# Memory_Chips_1_to_4.net
KiCad netlist of a schematic drawn in Altium Designer
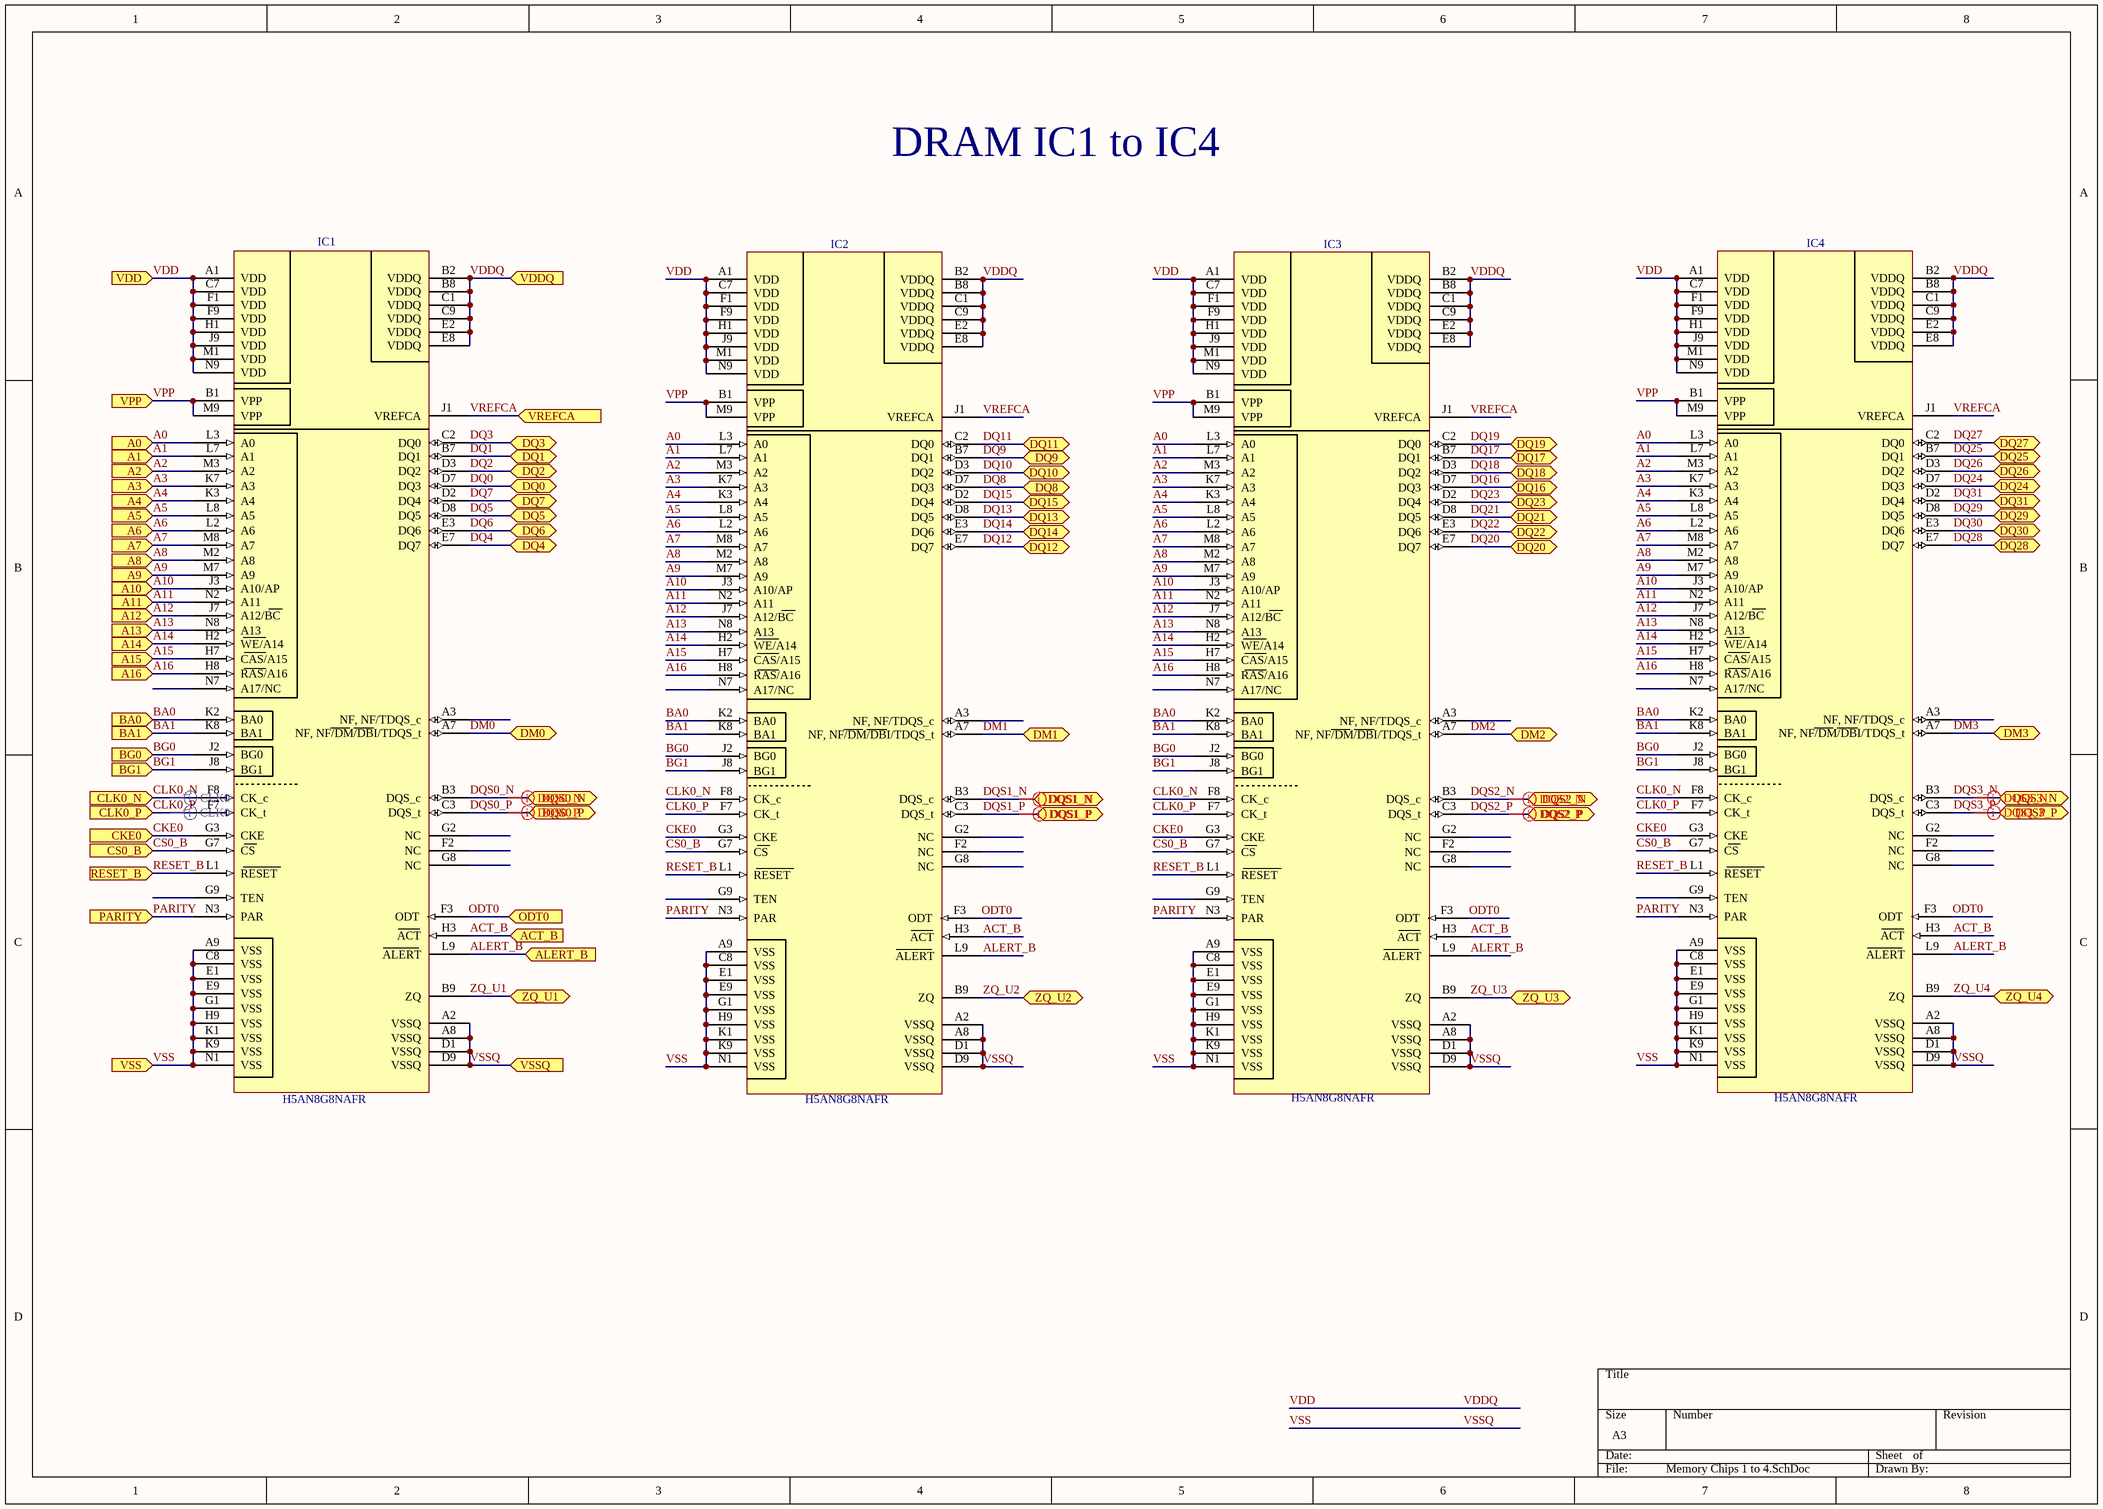
[diagram p0: Memory Chips 1 to 4.SchDoc]

(export (version "E")
  (design (tool "Eeschema 10.0.6"))
  (components
    (comp (ref "IC1")
      (value "H5AN8G8NAFR")
      (footprint "H5AN8G8NAFR")
      (libsource (lib "RouterIntLib") (part "H5AN8G8NAFR"))
    )
    (comp (ref "IC2")
      (value "H5AN8G8NAFR")
      (footprint "H5AN8G8NAFR")
      (libsource (lib "RouterIntLib") (part "H5AN8G8NAFR"))
    )
    (comp (ref "IC3")
      (value "H5AN8G8NAFR")
      (footprint "H5AN8G8NAFR")
      (libsource (lib "RouterIntLib") (part "H5AN8G8NAFR"))
    )
    (comp (ref "IC4")
      (value "H5AN8G8NAFR")
      (footprint "H5AN8G8NAFR")
      (libsource (lib "RouterIntLib") (part "H5AN8G8NAFR"))
    )
  )
  (nets
    (net (code "1") (name "/A0") (class "Default")
      (node (ref "IC1") (pin "L3") (pinfunction "A0_L3") (pintype "input"))
      (node (ref "IC2") (pin "L3") (pinfunction "A0_L3") (pintype "input"))
      (node (ref "IC3") (pin "L3") (pinfunction "A0_L3") (pintype "input"))
      (node (ref "IC4") (pin "L3") (pinfunction "A0_L3") (pintype "input"))
    )
    (net (code "2") (name "/A1") (class "Default")
      (node (ref "IC1") (pin "L7") (pinfunction "A1_L7") (pintype "input"))
      (node (ref "IC2") (pin "L7") (pinfunction "A1_L7") (pintype "input"))
      (node (ref "IC3") (pin "L7") (pinfunction "A1_L7") (pintype "input"))
      (node (ref "IC4") (pin "L7") (pinfunction "A1_L7") (pintype "input"))
    )
    (net (code "3") (name "/A2") (class "Default")
      (node (ref "IC1") (pin "M3") (pinfunction "A2_M3") (pintype "input"))
      (node (ref "IC2") (pin "M3") (pinfunction "A2_M3") (pintype "input"))
      (node (ref "IC3") (pin "M3") (pinfunction "A2_M3") (pintype "input"))
      (node (ref "IC4") (pin "M3") (pinfunction "A2_M3") (pintype "input"))
    )
    (net (code "4") (name "/A3") (class "Default")
      (node (ref "IC1") (pin "K7") (pinfunction "A3_K7") (pintype "input"))
      (node (ref "IC2") (pin "K7") (pinfunction "A3_K7") (pintype "input"))
      (node (ref "IC3") (pin "K7") (pinfunction "A3_K7") (pintype "input"))
      (node (ref "IC4") (pin "K7") (pinfunction "A3_K7") (pintype "input"))
    )
    (net (code "5") (name "/A4") (class "Default")
      (node (ref "IC1") (pin "K3") (pinfunction "A4_K3") (pintype "input"))
      (node (ref "IC2") (pin "K3") (pinfunction "A4_K3") (pintype "input"))
      (node (ref "IC3") (pin "K3") (pinfunction "A4_K3") (pintype "input"))
      (node (ref "IC4") (pin "K3") (pinfunction "A4_K3") (pintype "input"))
    )
    (net (code "6") (name "/A5") (class "Default")
      (node (ref "IC1") (pin "L8") (pinfunction "A5_L8") (pintype "input"))
      (node (ref "IC2") (pin "L8") (pinfunction "A5_L8") (pintype "input"))
      (node (ref "IC3") (pin "L8") (pinfunction "A5_L8") (pintype "input"))
      (node (ref "IC4") (pin "L8") (pinfunction "A5_L8") (pintype "input"))
    )
    (net (code "7") (name "/A6") (class "Default")
      (node (ref "IC1") (pin "L2") (pinfunction "A6_L2") (pintype "input"))
      (node (ref "IC2") (pin "L2") (pinfunction "A6_L2") (pintype "input"))
      (node (ref "IC3") (pin "L2") (pinfunction "A6_L2") (pintype "input"))
      (node (ref "IC4") (pin "L2") (pinfunction "A6_L2") (pintype "input"))
    )
    (net (code "8") (name "/A7") (class "Default")
      (node (ref "IC1") (pin "M8") (pinfunction "A7_M8") (pintype "input"))
      (node (ref "IC2") (pin "M8") (pinfunction "A7_M8") (pintype "input"))
      (node (ref "IC3") (pin "M8") (pinfunction "A7_M8") (pintype "input"))
      (node (ref "IC4") (pin "M8") (pinfunction "A7_M8") (pintype "input"))
    )
    (net (code "9") (name "/A8") (class "Default")
      (node (ref "IC1") (pin "M2") (pinfunction "A8_M2") (pintype "input"))
      (node (ref "IC2") (pin "M2") (pinfunction "A8_M2") (pintype "input"))
      (node (ref "IC3") (pin "M2") (pinfunction "A8_M2") (pintype "input"))
      (node (ref "IC4") (pin "M2") (pinfunction "A8_M2") (pintype "input"))
    )
    (net (code "10") (name "/A9") (class "Default")
      (node (ref "IC1") (pin "M7") (pinfunction "A9_M7") (pintype "input"))
      (node (ref "IC2") (pin "M7") (pinfunction "A9_M7") (pintype "input"))
      (node (ref "IC3") (pin "M7") (pinfunction "A9_M7") (pintype "input"))
      (node (ref "IC4") (pin "M7") (pinfunction "A9_M7") (pintype "input"))
    )
    (net (code "11") (name "/A10") (class "Default")
      (node (ref "IC1") (pin "J3") (pinfunction "A10/AP_J3") (pintype "input"))
      (node (ref "IC2") (pin "J3") (pinfunction "A10/AP_J3") (pintype "input"))
      (node (ref "IC3") (pin "J3") (pinfunction "A10/AP_J3") (pintype "input"))
      (node (ref "IC4") (pin "J3") (pinfunction "A10/AP_J3") (pintype "input"))
    )
    (net (code "12") (name "/A11") (class "Default")
      (node (ref "IC1") (pin "N2") (pinfunction "A11_N2") (pintype "input"))
      (node (ref "IC2") (pin "N2") (pinfunction "A11_N2") (pintype "input"))
      (node (ref "IC3") (pin "N2") (pinfunction "A11_N2") (pintype "input"))
      (node (ref "IC4") (pin "N2") (pinfunction "A11_N2") (pintype "input"))
    )
    (net (code "13") (name "/A12") (class "Default")
      (node (ref "IC1") (pin "J7") (pinfunction "A12/BC_J7") (pintype "input"))
      (node (ref "IC2") (pin "J7") (pinfunction "A12/BC_J7") (pintype "input"))
      (node (ref "IC3") (pin "J7") (pinfunction "A12/BC_J7") (pintype "input"))
      (node (ref "IC4") (pin "J7") (pinfunction "A12/BC_J7") (pintype "input"))
    )
    (net (code "14") (name "/A13") (class "Default")
      (node (ref "IC1") (pin "N8") (pinfunction "A13_N8") (pintype "input"))
      (node (ref "IC2") (pin "N8") (pinfunction "A13_N8") (pintype "input"))
      (node (ref "IC3") (pin "N8") (pinfunction "A13_N8") (pintype "input"))
      (node (ref "IC4") (pin "N8") (pinfunction "A13_N8") (pintype "input"))
    )
    (net (code "15") (name "/A14") (class "Default")
      (node (ref "IC1") (pin "H2") (pinfunction "WE/A14_H2") (pintype "input"))
      (node (ref "IC2") (pin "H2") (pinfunction "WE/A14_H2") (pintype "input"))
      (node (ref "IC3") (pin "H2") (pinfunction "WE/A14_H2") (pintype "input"))
      (node (ref "IC4") (pin "H2") (pinfunction "WE/A14_H2") (pintype "input"))
    )
    (net (code "16") (name "/A15") (class "Default")
      (node (ref "IC1") (pin "H7") (pinfunction "CAS/A15_H7") (pintype "input"))
      (node (ref "IC2") (pin "H7") (pinfunction "CAS/A15_H7") (pintype "input"))
      (node (ref "IC3") (pin "H7") (pinfunction "CAS/A15_H7") (pintype "input"))
      (node (ref "IC4") (pin "H7") (pinfunction "CAS/A15_H7") (pintype "input"))
    )
    (net (code "17") (name "/A16") (class "Default")
      (node (ref "IC1") (pin "H8") (pinfunction "RAS/A16_H8") (pintype "input"))
      (node (ref "IC2") (pin "H8") (pinfunction "RAS/A16_H8") (pintype "input"))
      (node (ref "IC3") (pin "H8") (pinfunction "RAS/A16_H8") (pintype "input"))
      (node (ref "IC4") (pin "H8") (pinfunction "RAS/A16_H8") (pintype "input"))
    )
    (net (code "18") (name "/ACT_B") (class "Default")
      (node (ref "IC1") (pin "H3") (pinfunction "ACT_H3") (pintype "input"))
      (node (ref "IC2") (pin "H3") (pinfunction "ACT_H3") (pintype "input"))
      (node (ref "IC3") (pin "H3") (pinfunction "ACT_H3") (pintype "input"))
      (node (ref "IC4") (pin "H3") (pinfunction "ACT_H3") (pintype "input"))
    )
    (net (code "19") (name "/ALERT_B") (class "Default")
      (node (ref "IC1") (pin "L9") (pinfunction "ALERT_L9") (pintype "passive"))
      (node (ref "IC2") (pin "L9") (pinfunction "ALERT_L9") (pintype "passive"))
      (node (ref "IC3") (pin "L9") (pinfunction "ALERT_L9") (pintype "passive"))
      (node (ref "IC4") (pin "L9") (pinfunction "ALERT_L9") (pintype "passive"))
    )
    (net (code "20") (name "/BA0") (class "Default")
      (node (ref "IC1") (pin "K2") (pinfunction "BA0_K2") (pintype "input"))
      (node (ref "IC2") (pin "K2") (pinfunction "BA0_K2") (pintype "input"))
      (node (ref "IC3") (pin "K2") (pinfunction "BA0_K2") (pintype "input"))
      (node (ref "IC4") (pin "K2") (pinfunction "BA0_K2") (pintype "input"))
    )
    (net (code "21") (name "/BA1") (class "Default")
      (node (ref "IC1") (pin "K8") (pinfunction "BA1_K8") (pintype "input"))
      (node (ref "IC2") (pin "K8") (pinfunction "BA1_K8") (pintype "input"))
      (node (ref "IC3") (pin "K8") (pinfunction "BA1_K8") (pintype "input"))
      (node (ref "IC4") (pin "K8") (pinfunction "BA1_K8") (pintype "input"))
    )
    (net (code "22") (name "/BG0") (class "Default")
      (node (ref "IC1") (pin "J2") (pinfunction "BG0_J2") (pintype "input"))
      (node (ref "IC2") (pin "J2") (pinfunction "BG0_J2") (pintype "input"))
      (node (ref "IC3") (pin "J2") (pinfunction "BG0_J2") (pintype "input"))
      (node (ref "IC4") (pin "J2") (pinfunction "BG0_J2") (pintype "input"))
    )
    (net (code "23") (name "/BG1") (class "Default")
      (node (ref "IC1") (pin "J8") (pinfunction "BG1_J8") (pintype "input"))
      (node (ref "IC2") (pin "J8") (pinfunction "BG1_J8") (pintype "input"))
      (node (ref "IC3") (pin "J8") (pinfunction "BG1_J8") (pintype "input"))
      (node (ref "IC4") (pin "J8") (pinfunction "BG1_J8") (pintype "input"))
    )
    (net (code "24") (name "/CKE0") (class "Default")
      (node (ref "IC1") (pin "G3") (pinfunction "CKE_G3") (pintype "input"))
      (node (ref "IC2") (pin "G3") (pinfunction "CKE_G3") (pintype "input"))
      (node (ref "IC3") (pin "G3") (pinfunction "CKE_G3") (pintype "input"))
      (node (ref "IC4") (pin "G3") (pinfunction "CKE_G3") (pintype "input"))
    )
    (net (code "25") (name "/CLK0_N") (class "Default")
      (node (ref "IC1") (pin "F8") (pinfunction "CK_c_F8") (pintype "input"))
      (node (ref "IC2") (pin "F8") (pinfunction "CK_c_F8") (pintype "input"))
      (node (ref "IC3") (pin "F8") (pinfunction "CK_c_F8") (pintype "input"))
      (node (ref "IC4") (pin "F8") (pinfunction "CK_c_F8") (pintype "input"))
    )
    (net (code "26") (name "/CLK0_P") (class "Default")
      (node (ref "IC1") (pin "F7") (pinfunction "CK_t_F7") (pintype "input"))
      (node (ref "IC2") (pin "F7") (pinfunction "CK_t_F7") (pintype "input"))
      (node (ref "IC3") (pin "F7") (pinfunction "CK_t_F7") (pintype "input"))
      (node (ref "IC4") (pin "F7") (pinfunction "CK_t_F7") (pintype "input"))
    )
    (net (code "27") (name "/CS0_B") (class "Default")
      (node (ref "IC1") (pin "G7") (pinfunction "CS_G7") (pintype "input"))
      (node (ref "IC2") (pin "G7") (pinfunction "CS_G7") (pintype "input"))
      (node (ref "IC3") (pin "G7") (pinfunction "CS_G7") (pintype "input"))
      (node (ref "IC4") (pin "G7") (pinfunction "CS_G7") (pintype "input"))
    )
    (net (code "28") (name "/DM0") (class "Default")
      (node (ref "IC1") (pin "A7") (pinfunction "NF,_NF/DM/DBI/TDQS_t_A7") (pintype "bidirectional"))
    )
    (net (code "29") (name "/DM1") (class "Default")
      (node (ref "IC2") (pin "A7") (pinfunction "NF,_NF/DM/DBI/TDQS_t_A7") (pintype "bidirectional"))
    )
    (net (code "30") (name "/DM2") (class "Default")
      (node (ref "IC3") (pin "A7") (pinfunction "NF,_NF/DM/DBI/TDQS_t_A7") (pintype "bidirectional"))
    )
    (net (code "31") (name "/DM3") (class "Default")
      (node (ref "IC4") (pin "A7") (pinfunction "NF,_NF/DM/DBI/TDQS_t_A7") (pintype "bidirectional"))
    )
    (net (code "32") (name "/DQ0") (class "Default")
      (node (ref "IC1") (pin "D7") (pinfunction "DQ3_D7") (pintype "bidirectional"))
    )
    (net (code "33") (name "/DQ1") (class "Default")
      (node (ref "IC1") (pin "B7") (pinfunction "DQ1_B7") (pintype "bidirectional"))
    )
    (net (code "34") (name "/DQ2") (class "Default")
      (node (ref "IC1") (pin "D3") (pinfunction "DQ2_D3") (pintype "bidirectional"))
    )
    (net (code "35") (name "/DQ3") (class "Default")
      (node (ref "IC1") (pin "C2") (pinfunction "DQ0_C2") (pintype "bidirectional"))
    )
    (net (code "36") (name "/DQ4") (class "Default")
      (node (ref "IC1") (pin "E7") (pinfunction "DQ7_E7") (pintype "bidirectional"))
    )
    (net (code "37") (name "/DQ5") (class "Default")
      (node (ref "IC1") (pin "D8") (pinfunction "DQ5_D8") (pintype "bidirectional"))
    )
    (net (code "38") (name "/DQ6") (class "Default")
      (node (ref "IC1") (pin "E3") (pinfunction "DQ6_E3") (pintype "bidirectional"))
    )
    (net (code "39") (name "/DQ7") (class "Default")
      (node (ref "IC1") (pin "D2") (pinfunction "DQ4_D2") (pintype "bidirectional"))
    )
    (net (code "40") (name "/DQ8") (class "Default")
      (node (ref "IC2") (pin "D7") (pinfunction "DQ3_D7") (pintype "bidirectional"))
    )
    (net (code "41") (name "/DQ9") (class "Default")
      (node (ref "IC2") (pin "B7") (pinfunction "DQ1_B7") (pintype "bidirectional"))
    )
    (net (code "42") (name "/DQ10") (class "Default")
      (node (ref "IC2") (pin "D3") (pinfunction "DQ2_D3") (pintype "bidirectional"))
    )
    (net (code "43") (name "/DQ11") (class "Default")
      (node (ref "IC2") (pin "C2") (pinfunction "DQ0_C2") (pintype "bidirectional"))
    )
    (net (code "44") (name "/DQ12") (class "Default")
      (node (ref "IC2") (pin "E7") (pinfunction "DQ7_E7") (pintype "bidirectional"))
    )
    (net (code "45") (name "/DQ13") (class "Default")
      (node (ref "IC2") (pin "D8") (pinfunction "DQ5_D8") (pintype "bidirectional"))
    )
    (net (code "46") (name "/DQ14") (class "Default")
      (node (ref "IC2") (pin "E3") (pinfunction "DQ6_E3") (pintype "bidirectional"))
    )
    (net (code "47") (name "/DQ15") (class "Default")
      (node (ref "IC2") (pin "D2") (pinfunction "DQ4_D2") (pintype "bidirectional"))
    )
    (net (code "48") (name "/DQ16") (class "Default")
      (node (ref "IC3") (pin "D7") (pinfunction "DQ3_D7") (pintype "bidirectional"))
    )
    (net (code "49") (name "/DQ17") (class "Default")
      (node (ref "IC3") (pin "B7") (pinfunction "DQ1_B7") (pintype "bidirectional"))
    )
    (net (code "50") (name "/DQ18") (class "Default")
      (node (ref "IC3") (pin "D3") (pinfunction "DQ2_D3") (pintype "bidirectional"))
    )
    (net (code "51") (name "/DQ19") (class "Default")
      (node (ref "IC3") (pin "C2") (pinfunction "DQ0_C2") (pintype "bidirectional"))
    )
    (net (code "52") (name "/DQ20") (class "Default")
      (node (ref "IC3") (pin "E7") (pinfunction "DQ7_E7") (pintype "bidirectional"))
    )
    (net (code "53") (name "/DQ21") (class "Default")
      (node (ref "IC3") (pin "D8") (pinfunction "DQ5_D8") (pintype "bidirectional"))
    )
    (net (code "54") (name "/DQ22") (class "Default")
      (node (ref "IC3") (pin "E3") (pinfunction "DQ6_E3") (pintype "bidirectional"))
    )
    (net (code "55") (name "/DQ23") (class "Default")
      (node (ref "IC3") (pin "D2") (pinfunction "DQ4_D2") (pintype "bidirectional"))
    )
    (net (code "56") (name "/DQ24") (class "Default")
      (node (ref "IC4") (pin "D7") (pinfunction "DQ3_D7") (pintype "bidirectional"))
    )
    (net (code "57") (name "/DQ25") (class "Default")
      (node (ref "IC4") (pin "B7") (pinfunction "DQ1_B7") (pintype "bidirectional"))
    )
    (net (code "58") (name "/DQ26") (class "Default")
      (node (ref "IC4") (pin "D3") (pinfunction "DQ2_D3") (pintype "bidirectional"))
    )
    (net (code "59") (name "/DQ27") (class "Default")
      (node (ref "IC4") (pin "C2") (pinfunction "DQ0_C2") (pintype "bidirectional"))
    )
    (net (code "60") (name "/DQ28") (class "Default")
      (node (ref "IC4") (pin "E7") (pinfunction "DQ7_E7") (pintype "bidirectional"))
    )
    (net (code "61") (name "/DQ29") (class "Default")
      (node (ref "IC4") (pin "D8") (pinfunction "DQ5_D8") (pintype "bidirectional"))
    )
    (net (code "62") (name "/DQ30") (class "Default")
      (node (ref "IC4") (pin "E3") (pinfunction "DQ6_E3") (pintype "bidirectional"))
    )
    (net (code "63") (name "/DQ31") (class "Default")
      (node (ref "IC4") (pin "D2") (pinfunction "DQ4_D2") (pintype "bidirectional"))
    )
    (net (code "64") (name "/DQS0_N") (class "Default")
      (node (ref "IC1") (pin "B3") (pinfunction "DQS_c_B3") (pintype "bidirectional"))
    )
    (net (code "65") (name "/DQS0_P") (class "Default")
      (node (ref "IC1") (pin "C3") (pinfunction "DQS_t_C3") (pintype "bidirectional"))
    )
    (net (code "66") (name "/DQS1_N") (class "Default")
      (node (ref "IC2") (pin "B3") (pinfunction "DQS_c_B3") (pintype "bidirectional"))
    )
    (net (code "67") (name "/DQS1_P") (class "Default")
      (node (ref "IC2") (pin "C3") (pinfunction "DQS_t_C3") (pintype "bidirectional"))
    )
    (net (code "68") (name "/DQS2_N") (class "Default")
      (node (ref "IC3") (pin "B3") (pinfunction "DQS_c_B3") (pintype "bidirectional"))
    )
    (net (code "69") (name "/DQS2_P") (class "Default")
      (node (ref "IC3") (pin "C3") (pinfunction "DQS_t_C3") (pintype "bidirectional"))
    )
    (net (code "70") (name "/DQS3_N") (class "Default")
      (node (ref "IC4") (pin "B3") (pinfunction "DQS_c_B3") (pintype "bidirectional"))
    )
    (net (code "71") (name "/DQS3_P") (class "Default")
      (node (ref "IC4") (pin "C3") (pinfunction "DQS_t_C3") (pintype "bidirectional"))
    )
    (net (code "72") (name "/ODT0") (class "Default")
      (node (ref "IC1") (pin "F3") (pinfunction "ODT_F3") (pintype "input"))
      (node (ref "IC2") (pin "F3") (pinfunction "ODT_F3") (pintype "input"))
      (node (ref "IC3") (pin "F3") (pinfunction "ODT_F3") (pintype "input"))
      (node (ref "IC4") (pin "F3") (pinfunction "ODT_F3") (pintype "input"))
    )
    (net (code "73") (name "/PARITY") (class "Default")
      (node (ref "IC1") (pin "N3") (pinfunction "PAR_N3") (pintype "input"))
      (node (ref "IC2") (pin "N3") (pinfunction "PAR_N3") (pintype "input"))
      (node (ref "IC3") (pin "N3") (pinfunction "PAR_N3") (pintype "input"))
      (node (ref "IC4") (pin "N3") (pinfunction "PAR_N3") (pintype "input"))
    )
    (net (code "74") (name "/RESET_B") (class "Default")
      (node (ref "IC1") (pin "L1") (pinfunction "RESET_L1") (pintype "input"))
      (node (ref "IC2") (pin "L1") (pinfunction "RESET_L1") (pintype "input"))
      (node (ref "IC3") (pin "L1") (pinfunction "RESET_L1") (pintype "input"))
      (node (ref "IC4") (pin "L1") (pinfunction "RESET_L1") (pintype "input"))
    )
    (net (code "75") (name "/VDD") (class "Default")
      (node (ref "IC1") (pin "A1") (pinfunction "VDD_A1") (pintype "power_in"))
      (node (ref "IC1") (pin "B2") (pinfunction "VDDQ_B2") (pintype "power_in"))
      (node (ref "IC1") (pin "B8") (pinfunction "VDDQ_B8") (pintype "power_in"))
      (node (ref "IC1") (pin "C1") (pinfunction "VDDQ_C1") (pintype "power_in"))
      (node (ref "IC1") (pin "C7") (pinfunction "VDD_C7") (pintype "power_in"))
      (node (ref "IC1") (pin "C9") (pinfunction "VDDQ_C9") (pintype "power_in"))
      (node (ref "IC1") (pin "E2") (pinfunction "VDDQ_E2") (pintype "power_in"))
      (node (ref "IC1") (pin "E8") (pinfunction "VDDQ_E8") (pintype "power_in"))
      (node (ref "IC1") (pin "F1") (pinfunction "VDD_F1") (pintype "power_in"))
      (node (ref "IC1") (pin "F9") (pinfunction "VDD_F9") (pintype "power_in"))
      (node (ref "IC1") (pin "H1") (pinfunction "VDD_H1") (pintype "power_in"))
      (node (ref "IC1") (pin "J9") (pinfunction "VDD_J9") (pintype "power_in"))
      (node (ref "IC1") (pin "M1") (pinfunction "VDD_M1") (pintype "power_in"))
      (node (ref "IC1") (pin "N9") (pinfunction "VDD_N9") (pintype "power_in"))
      (node (ref "IC2") (pin "A1") (pinfunction "VDD_A1") (pintype "power_in"))
      (node (ref "IC2") (pin "B2") (pinfunction "VDDQ_B2") (pintype "power_in"))
      (node (ref "IC2") (pin "B8") (pinfunction "VDDQ_B8") (pintype "power_in"))
      (node (ref "IC2") (pin "C1") (pinfunction "VDDQ_C1") (pintype "power_in"))
      (node (ref "IC2") (pin "C7") (pinfunction "VDD_C7") (pintype "power_in"))
      (node (ref "IC2") (pin "C9") (pinfunction "VDDQ_C9") (pintype "power_in"))
      (node (ref "IC2") (pin "E2") (pinfunction "VDDQ_E2") (pintype "power_in"))
      (node (ref "IC2") (pin "E8") (pinfunction "VDDQ_E8") (pintype "power_in"))
      (node (ref "IC2") (pin "F1") (pinfunction "VDD_F1") (pintype "power_in"))
      (node (ref "IC2") (pin "F9") (pinfunction "VDD_F9") (pintype "power_in"))
      (node (ref "IC2") (pin "H1") (pinfunction "VDD_H1") (pintype "power_in"))
      (node (ref "IC2") (pin "J9") (pinfunction "VDD_J9") (pintype "power_in"))
      (node (ref "IC2") (pin "M1") (pinfunction "VDD_M1") (pintype "power_in"))
      (node (ref "IC2") (pin "N9") (pinfunction "VDD_N9") (pintype "power_in"))
      (node (ref "IC3") (pin "A1") (pinfunction "VDD_A1") (pintype "power_in"))
      (node (ref "IC3") (pin "B2") (pinfunction "VDDQ_B2") (pintype "power_in"))
      (node (ref "IC3") (pin "B8") (pinfunction "VDDQ_B8") (pintype "power_in"))
      (node (ref "IC3") (pin "C1") (pinfunction "VDDQ_C1") (pintype "power_in"))
      (node (ref "IC3") (pin "C7") (pinfunction "VDD_C7") (pintype "power_in"))
      (node (ref "IC3") (pin "C9") (pinfunction "VDDQ_C9") (pintype "power_in"))
      (node (ref "IC3") (pin "E2") (pinfunction "VDDQ_E2") (pintype "power_in"))
      (node (ref "IC3") (pin "E8") (pinfunction "VDDQ_E8") (pintype "power_in"))
      (node (ref "IC3") (pin "F1") (pinfunction "VDD_F1") (pintype "power_in"))
      (node (ref "IC3") (pin "F9") (pinfunction "VDD_F9") (pintype "power_in"))
      (node (ref "IC3") (pin "H1") (pinfunction "VDD_H1") (pintype "power_in"))
      (node (ref "IC3") (pin "J9") (pinfunction "VDD_J9") (pintype "power_in"))
      (node (ref "IC3") (pin "M1") (pinfunction "VDD_M1") (pintype "power_in"))
      (node (ref "IC3") (pin "N9") (pinfunction "VDD_N9") (pintype "power_in"))
      (node (ref "IC4") (pin "A1") (pinfunction "VDD_A1") (pintype "power_in"))
      (node (ref "IC4") (pin "B2") (pinfunction "VDDQ_B2") (pintype "power_in"))
      (node (ref "IC4") (pin "B8") (pinfunction "VDDQ_B8") (pintype "power_in"))
      (node (ref "IC4") (pin "C1") (pinfunction "VDDQ_C1") (pintype "power_in"))
      (node (ref "IC4") (pin "C7") (pinfunction "VDD_C7") (pintype "power_in"))
      (node (ref "IC4") (pin "C9") (pinfunction "VDDQ_C9") (pintype "power_in"))
      (node (ref "IC4") (pin "E2") (pinfunction "VDDQ_E2") (pintype "power_in"))
      (node (ref "IC4") (pin "E8") (pinfunction "VDDQ_E8") (pintype "power_in"))
      (node (ref "IC4") (pin "F1") (pinfunction "VDD_F1") (pintype "power_in"))
      (node (ref "IC4") (pin "F9") (pinfunction "VDD_F9") (pintype "power_in"))
      (node (ref "IC4") (pin "H1") (pinfunction "VDD_H1") (pintype "power_in"))
      (node (ref "IC4") (pin "J9") (pinfunction "VDD_J9") (pintype "power_in"))
      (node (ref "IC4") (pin "M1") (pinfunction "VDD_M1") (pintype "power_in"))
      (node (ref "IC4") (pin "N9") (pinfunction "VDD_N9") (pintype "power_in"))
    )
    (net (code "76") (name "/VPP") (class "Default")
      (node (ref "IC1") (pin "B1") (pinfunction "VPP_B1") (pintype "power_in"))
      (node (ref "IC1") (pin "M9") (pinfunction "VPP_M9") (pintype "power_in"))
      (node (ref "IC2") (pin "B1") (pinfunction "VPP_B1") (pintype "power_in"))
      (node (ref "IC2") (pin "M9") (pinfunction "VPP_M9") (pintype "power_in"))
      (node (ref "IC3") (pin "B1") (pinfunction "VPP_B1") (pintype "power_in"))
      (node (ref "IC3") (pin "M9") (pinfunction "VPP_M9") (pintype "power_in"))
      (node (ref "IC4") (pin "B1") (pinfunction "VPP_B1") (pintype "power_in"))
      (node (ref "IC4") (pin "M9") (pinfunction "VPP_M9") (pintype "power_in"))
    )
    (net (code "77") (name "/VREFCA") (class "Default")
      (node (ref "IC1") (pin "J1") (pinfunction "VREFCA_J1") (pintype "power_in"))
      (node (ref "IC2") (pin "J1") (pinfunction "VREFCA_J1") (pintype "power_in"))
      (node (ref "IC3") (pin "J1") (pinfunction "VREFCA_J1") (pintype "power_in"))
      (node (ref "IC4") (pin "J1") (pinfunction "VREFCA_J1") (pintype "power_in"))
    )
    (net (code "78") (name "/VSS") (class "Default")
      (node (ref "IC1") (pin "A2") (pinfunction "VSSQ_A2") (pintype "power_in"))
      (node (ref "IC1") (pin "A8") (pinfunction "VSSQ_A8") (pintype "power_in"))
      (node (ref "IC1") (pin "A9") (pinfunction "VSS_A9") (pintype "passive"))
      (node (ref "IC1") (pin "C8") (pinfunction "VSS_C8") (pintype "passive"))
      (node (ref "IC1") (pin "D1") (pinfunction "VSSQ_D1") (pintype "power_in"))
      (node (ref "IC1") (pin "D9") (pinfunction "VSSQ_D9") (pintype "power_in"))
      (node (ref "IC1") (pin "E1") (pinfunction "VSS_E1") (pintype "passive"))
      (node (ref "IC1") (pin "E9") (pinfunction "VSS_E9") (pintype "passive"))
      (node (ref "IC1") (pin "G1") (pinfunction "VSS_G1") (pintype "passive"))
      (node (ref "IC1") (pin "H9") (pinfunction "VSS_H9") (pintype "passive"))
      (node (ref "IC1") (pin "K1") (pinfunction "VSS_K1") (pintype "passive"))
      (node (ref "IC1") (pin "K9") (pinfunction "VSS_K9") (pintype "passive"))
      (node (ref "IC1") (pin "N1") (pinfunction "VSS_N1") (pintype "passive"))
      (node (ref "IC2") (pin "A2") (pinfunction "VSSQ_A2") (pintype "power_in"))
      (node (ref "IC2") (pin "A8") (pinfunction "VSSQ_A8") (pintype "power_in"))
      (node (ref "IC2") (pin "A9") (pinfunction "VSS_A9") (pintype "passive"))
      (node (ref "IC2") (pin "C8") (pinfunction "VSS_C8") (pintype "passive"))
      (node (ref "IC2") (pin "D1") (pinfunction "VSSQ_D1") (pintype "power_in"))
      (node (ref "IC2") (pin "D9") (pinfunction "VSSQ_D9") (pintype "power_in"))
      (node (ref "IC2") (pin "E1") (pinfunction "VSS_E1") (pintype "passive"))
      (node (ref "IC2") (pin "E9") (pinfunction "VSS_E9") (pintype "passive"))
      (node (ref "IC2") (pin "G1") (pinfunction "VSS_G1") (pintype "passive"))
      (node (ref "IC2") (pin "H9") (pinfunction "VSS_H9") (pintype "passive"))
      (node (ref "IC2") (pin "K1") (pinfunction "VSS_K1") (pintype "passive"))
      (node (ref "IC2") (pin "K9") (pinfunction "VSS_K9") (pintype "passive"))
      (node (ref "IC2") (pin "N1") (pinfunction "VSS_N1") (pintype "passive"))
      (node (ref "IC3") (pin "A2") (pinfunction "VSSQ_A2") (pintype "power_in"))
      (node (ref "IC3") (pin "A8") (pinfunction "VSSQ_A8") (pintype "power_in"))
      (node (ref "IC3") (pin "A9") (pinfunction "VSS_A9") (pintype "passive"))
      (node (ref "IC3") (pin "C8") (pinfunction "VSS_C8") (pintype "passive"))
      (node (ref "IC3") (pin "D1") (pinfunction "VSSQ_D1") (pintype "power_in"))
      (node (ref "IC3") (pin "D9") (pinfunction "VSSQ_D9") (pintype "power_in"))
      (node (ref "IC3") (pin "E1") (pinfunction "VSS_E1") (pintype "passive"))
      (node (ref "IC3") (pin "E9") (pinfunction "VSS_E9") (pintype "passive"))
      (node (ref "IC3") (pin "G1") (pinfunction "VSS_G1") (pintype "passive"))
      (node (ref "IC3") (pin "H9") (pinfunction "VSS_H9") (pintype "passive"))
      (node (ref "IC3") (pin "K1") (pinfunction "VSS_K1") (pintype "passive"))
      (node (ref "IC3") (pin "K9") (pinfunction "VSS_K9") (pintype "passive"))
      (node (ref "IC3") (pin "N1") (pinfunction "VSS_N1") (pintype "passive"))
      (node (ref "IC4") (pin "A2") (pinfunction "VSSQ_A2") (pintype "power_in"))
      (node (ref "IC4") (pin "A8") (pinfunction "VSSQ_A8") (pintype "power_in"))
      (node (ref "IC4") (pin "A9") (pinfunction "VSS_A9") (pintype "passive"))
      (node (ref "IC4") (pin "C8") (pinfunction "VSS_C8") (pintype "passive"))
      (node (ref "IC4") (pin "D1") (pinfunction "VSSQ_D1") (pintype "power_in"))
      (node (ref "IC4") (pin "D9") (pinfunction "VSSQ_D9") (pintype "power_in"))
      (node (ref "IC4") (pin "E1") (pinfunction "VSS_E1") (pintype "passive"))
      (node (ref "IC4") (pin "E9") (pinfunction "VSS_E9") (pintype "passive"))
      (node (ref "IC4") (pin "G1") (pinfunction "VSS_G1") (pintype "passive"))
      (node (ref "IC4") (pin "H9") (pinfunction "VSS_H9") (pintype "passive"))
      (node (ref "IC4") (pin "K1") (pinfunction "VSS_K1") (pintype "passive"))
      (node (ref "IC4") (pin "K9") (pinfunction "VSS_K9") (pintype "passive"))
      (node (ref "IC4") (pin "N1") (pinfunction "VSS_N1") (pintype "passive"))
    )
    (net (code "79") (name "/ZQ_U1") (class "Default")
      (node (ref "IC1") (pin "B9") (pinfunction "ZQ_B9") (pintype "passive"))
    )
    (net (code "80") (name "/ZQ_U2") (class "Default")
      (node (ref "IC2") (pin "B9") (pinfunction "ZQ_B9") (pintype "passive"))
    )
    (net (code "81") (name "/ZQ_U3") (class "Default")
      (node (ref "IC3") (pin "B9") (pinfunction "ZQ_B9") (pintype "passive"))
    )
    (net (code "82") (name "/ZQ_U4") (class "Default")
      (node (ref "IC4") (pin "B9") (pinfunction "ZQ_B9") (pintype "passive"))
    )
    (net (code "83") (name "unconnected-(IC1-A17{slash}NC-PadN7)") (class "Default")
      (node (ref "IC1") (pin "N7") (pinfunction "A17/NC_N7") (pintype "input"))
    )
    (net (code "84") (name "unconnected-(IC1-NC-PadF2)") (class "Default")
      (node (ref "IC1") (pin "F2") (pinfunction "NC_F2") (pintype "passive"))
    )
    (net (code "85") (name "unconnected-(IC1-NC-PadG2)") (class "Default")
      (node (ref "IC1") (pin "G2") (pinfunction "NC_G2") (pintype "passive"))
    )
    (net (code "86") (name "unconnected-(IC1-NC-PadG8)") (class "Default")
      (node (ref "IC1") (pin "G8") (pinfunction "NC_G8") (pintype "passive"))
    )
    (net (code "87") (name "unconnected-(IC1-NF,_NF{slash}TDQS_c-PadA3)") (class "Default")
      (node (ref "IC1") (pin "A3") (pinfunction "NF,_NF/TDQS_c_A3") (pintype "bidirectional"))
    )
    (net (code "88") (name "unconnected-(IC1-TEN-PadG9)") (class "Default")
      (node (ref "IC1") (pin "G9") (pinfunction "TEN_G9") (pintype "input"))
    )
    (net (code "89") (name "unconnected-(IC2-A17{slash}NC-PadN7)") (class "Default")
      (node (ref "IC2") (pin "N7") (pinfunction "A17/NC_N7") (pintype "input"))
    )
    (net (code "90") (name "unconnected-(IC2-NC-PadF2)") (class "Default")
      (node (ref "IC2") (pin "F2") (pinfunction "NC_F2") (pintype "passive"))
    )
    (net (code "91") (name "unconnected-(IC2-NC-PadG2)") (class "Default")
      (node (ref "IC2") (pin "G2") (pinfunction "NC_G2") (pintype "passive"))
    )
    (net (code "92") (name "unconnected-(IC2-NC-PadG8)") (class "Default")
      (node (ref "IC2") (pin "G8") (pinfunction "NC_G8") (pintype "passive"))
    )
    (net (code "93") (name "unconnected-(IC2-NF,_NF{slash}TDQS_c-PadA3)") (class "Default")
      (node (ref "IC2") (pin "A3") (pinfunction "NF,_NF/TDQS_c_A3") (pintype "bidirectional"))
    )
    (net (code "94") (name "unconnected-(IC2-TEN-PadG9)") (class "Default")
      (node (ref "IC2") (pin "G9") (pinfunction "TEN_G9") (pintype "input"))
    )
    (net (code "95") (name "unconnected-(IC3-A17{slash}NC-PadN7)") (class "Default")
      (node (ref "IC3") (pin "N7") (pinfunction "A17/NC_N7") (pintype "input"))
    )
    (net (code "96") (name "unconnected-(IC3-NC-PadF2)") (class "Default")
      (node (ref "IC3") (pin "F2") (pinfunction "NC_F2") (pintype "passive"))
    )
    (net (code "97") (name "unconnected-(IC3-NC-PadG2)") (class "Default")
      (node (ref "IC3") (pin "G2") (pinfunction "NC_G2") (pintype "passive"))
    )
    (net (code "98") (name "unconnected-(IC3-NC-PadG8)") (class "Default")
      (node (ref "IC3") (pin "G8") (pinfunction "NC_G8") (pintype "passive"))
    )
    (net (code "99") (name "unconnected-(IC3-NF,_NF{slash}TDQS_c-PadA3)") (class "Default")
      (node (ref "IC3") (pin "A3") (pinfunction "NF,_NF/TDQS_c_A3") (pintype "bidirectional"))
    )
    (net (code "100") (name "unconnected-(IC3-TEN-PadG9)") (class "Default")
      (node (ref "IC3") (pin "G9") (pinfunction "TEN_G9") (pintype "input"))
    )
    (net (code "101") (name "unconnected-(IC4-A17{slash}NC-PadN7)") (class "Default")
      (node (ref "IC4") (pin "N7") (pinfunction "A17/NC_N7") (pintype "input"))
    )
    (net (code "102") (name "unconnected-(IC4-NC-PadF2)") (class "Default")
      (node (ref "IC4") (pin "F2") (pinfunction "NC_F2") (pintype "passive"))
    )
    (net (code "103") (name "unconnected-(IC4-NC-PadG2)") (class "Default")
      (node (ref "IC4") (pin "G2") (pinfunction "NC_G2") (pintype "passive"))
    )
    (net (code "104") (name "unconnected-(IC4-NC-PadG8)") (class "Default")
      (node (ref "IC4") (pin "G8") (pinfunction "NC_G8") (pintype "passive"))
    )
    (net (code "105") (name "unconnected-(IC4-NF,_NF{slash}TDQS_c-PadA3)") (class "Default")
      (node (ref "IC4") (pin "A3") (pinfunction "NF,_NF/TDQS_c_A3") (pintype "bidirectional"))
    )
    (net (code "106") (name "unconnected-(IC4-TEN-PadG9)") (class "Default")
      (node (ref "IC4") (pin "G9") (pinfunction "TEN_G9") (pintype "input"))
    )
  )
)
